# guhPLC_dimmModule_V0_2.net
KiCad netlist of a schematic drawn in EAGLE
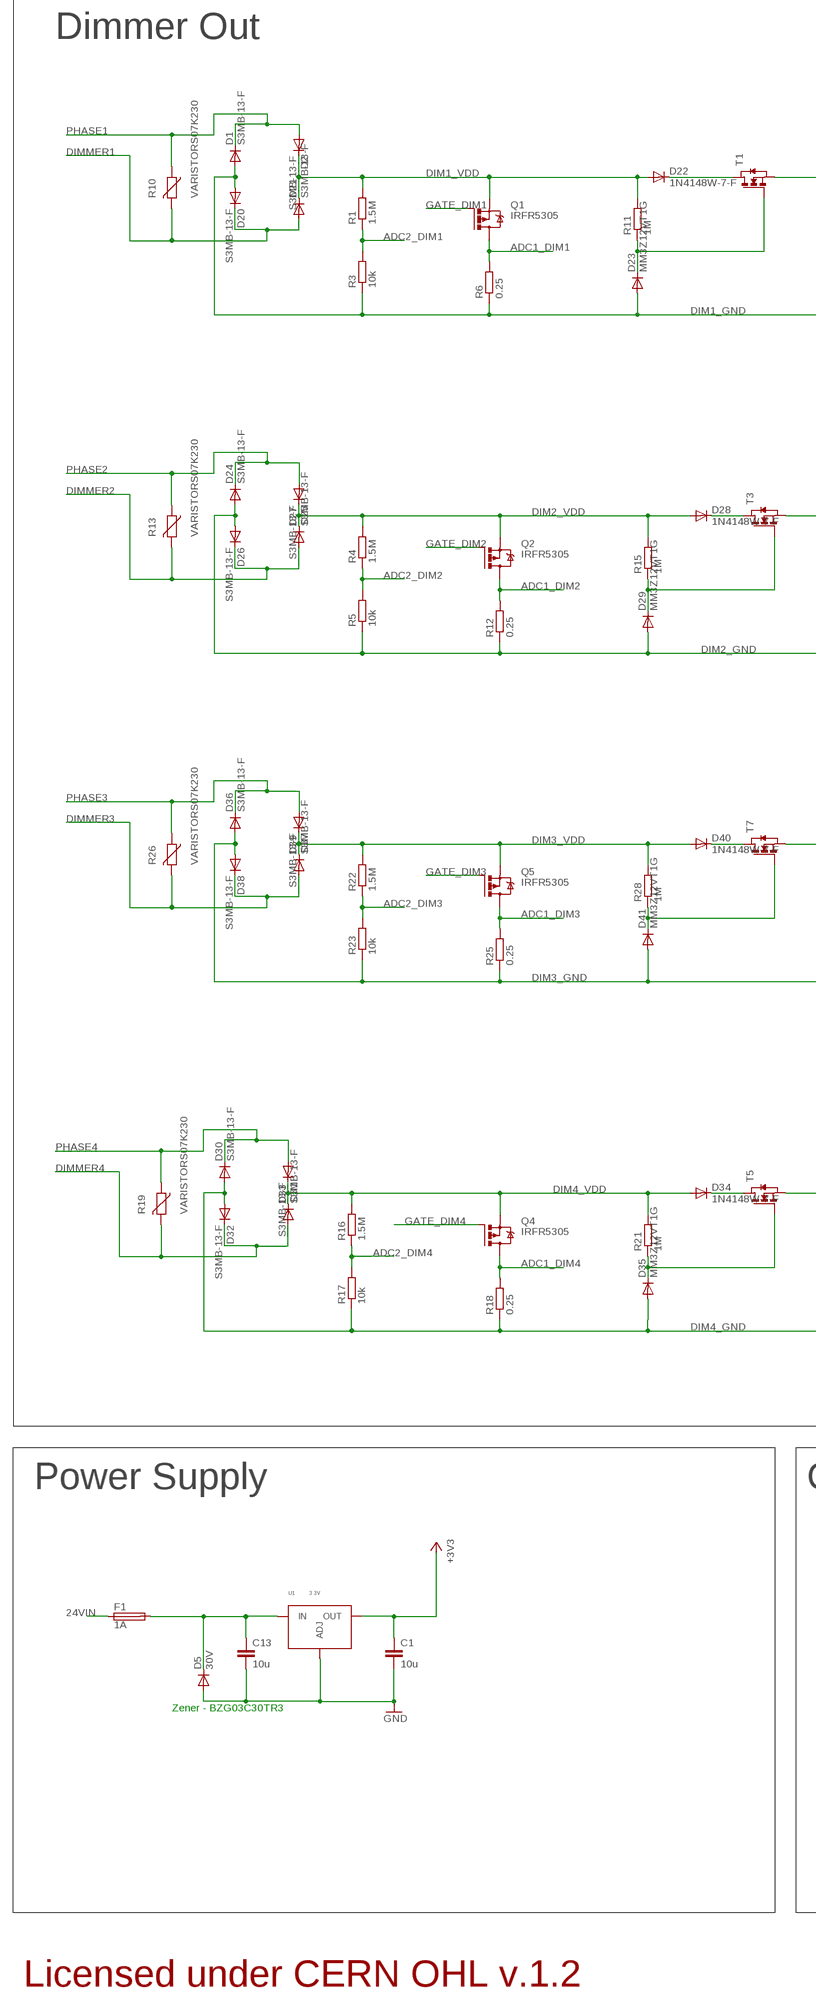
[diagram p0: schematic, sheet 1, part 1 of 2]
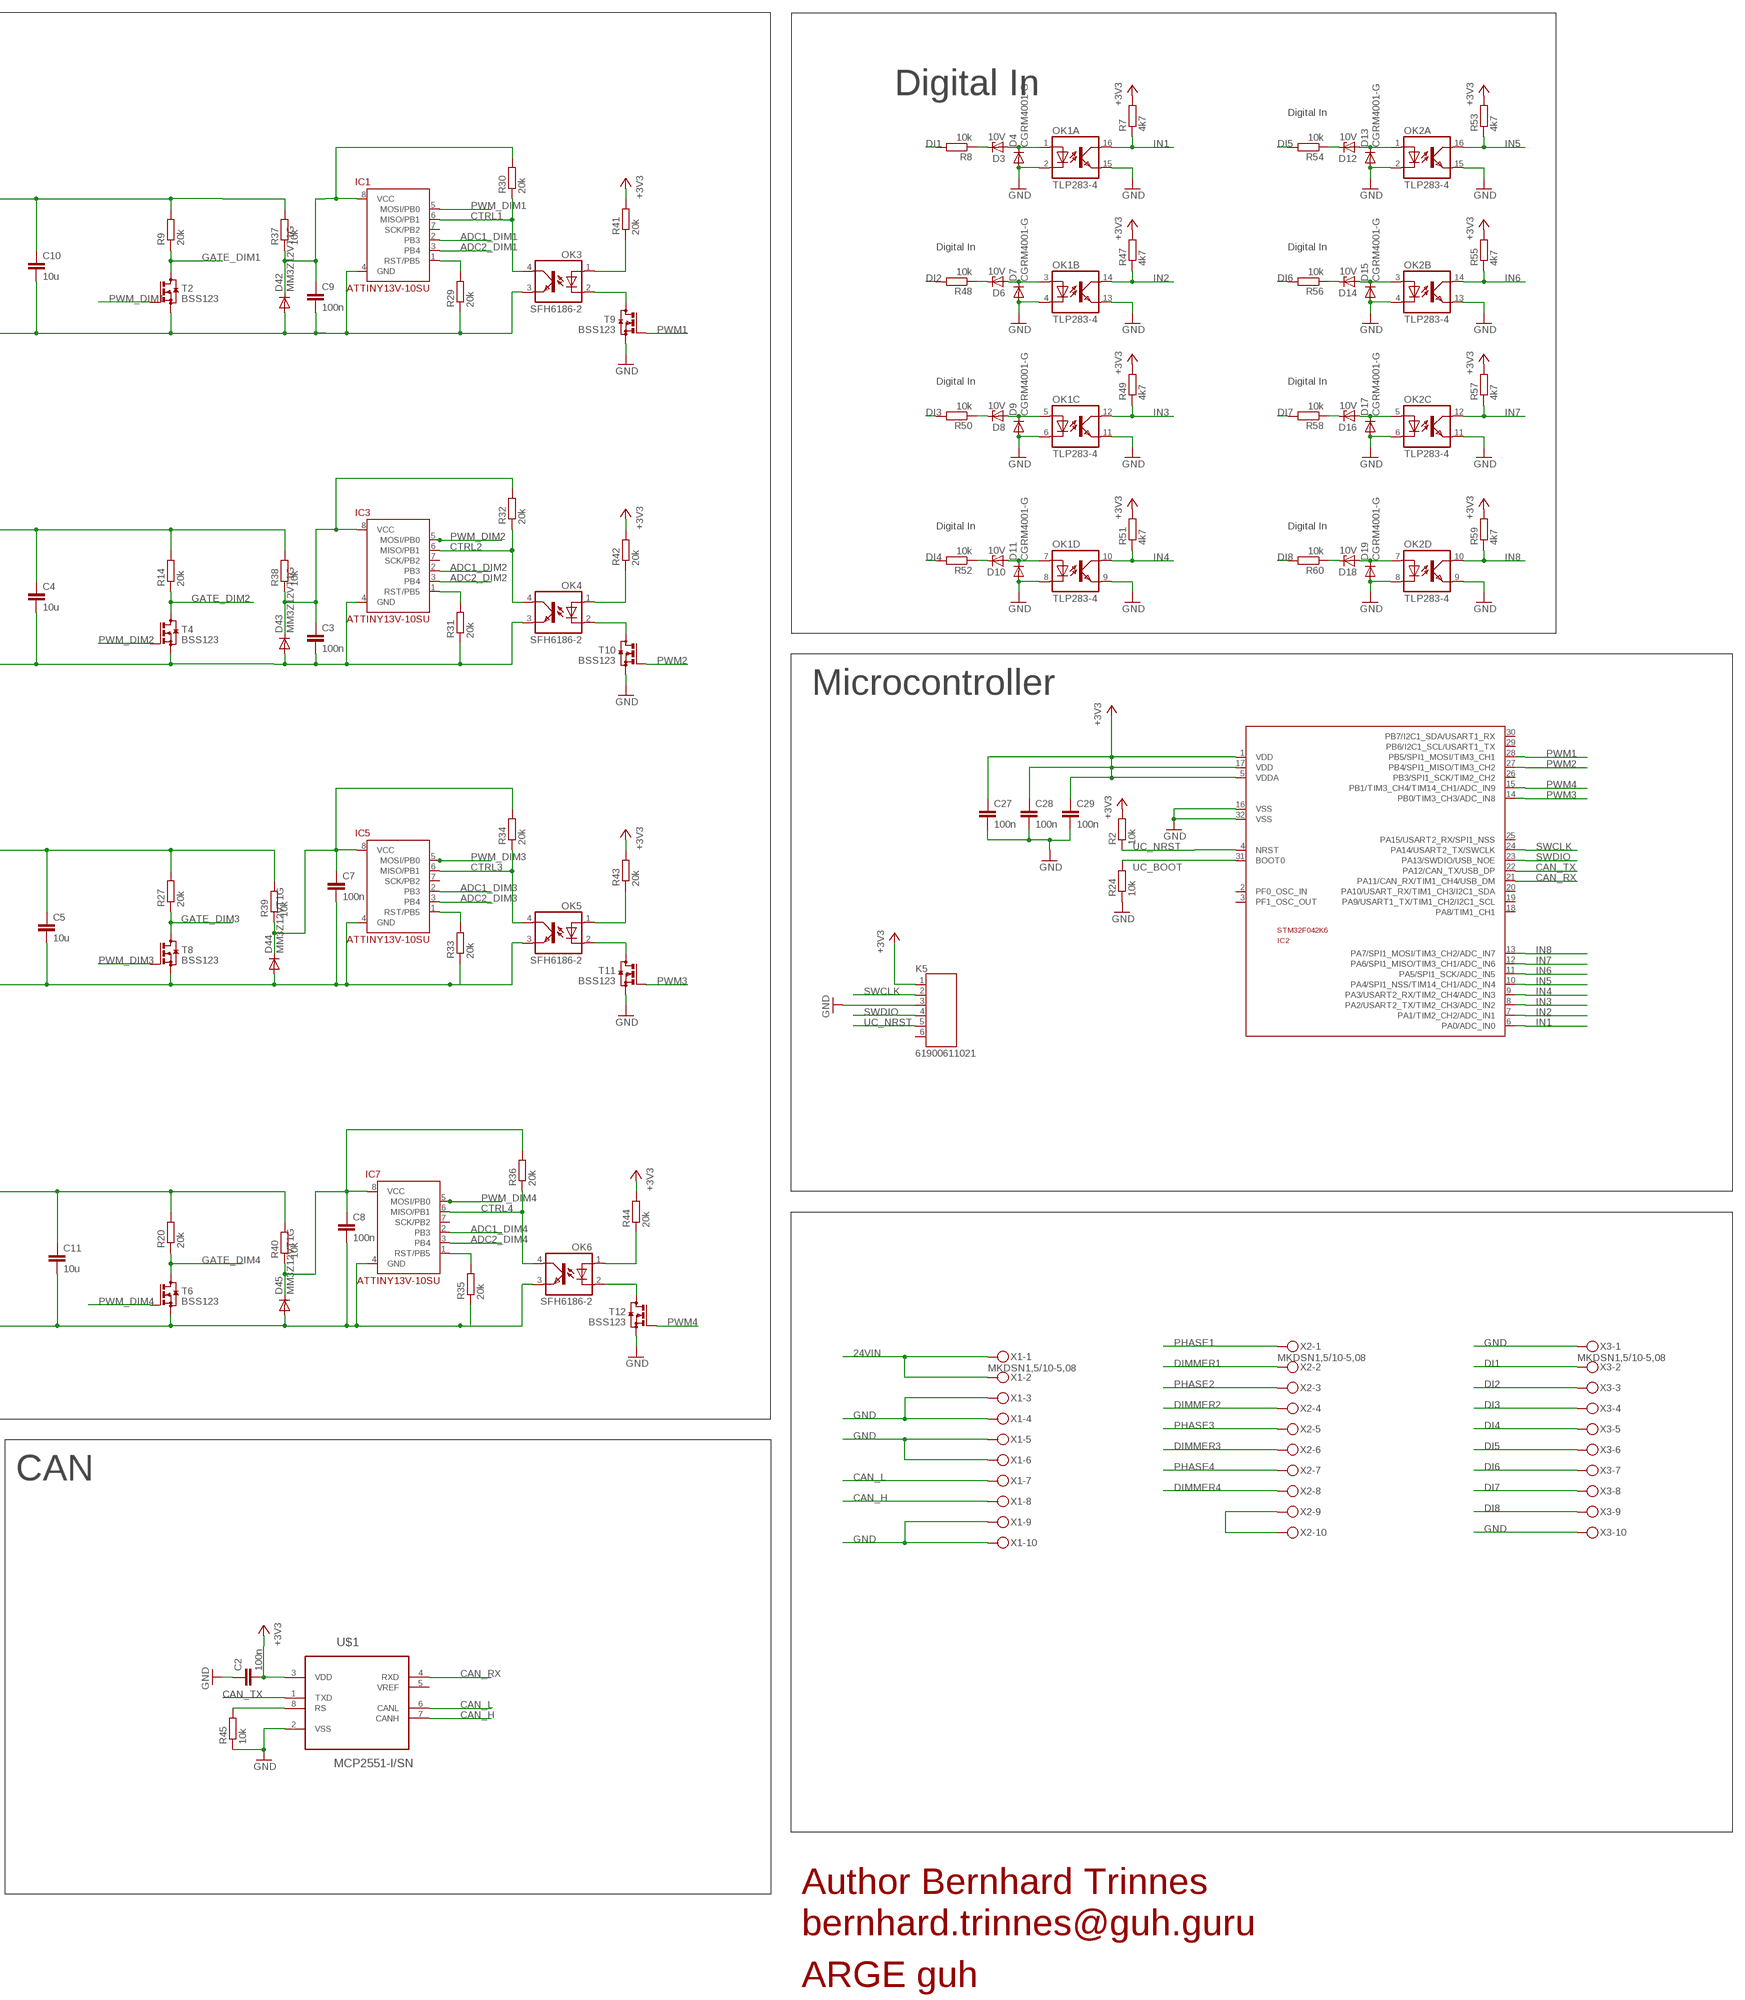
[diagram p1: schematic, sheet 1, part 2 of 2]

(export (version "E")
  (design (tool "Eeschema 10.0.6"))
  (components
    (comp (ref "C1")
      (value "10u")
      (footprint "eagle-import:C1206")
      (libsource (lib "eagle-import") (part "C-EUC1206"))
    )
    (comp (ref "C2")
      (value "100n")
      (footprint "eagle-import:C0603")
      (libsource (lib "eagle-import") (part "C-EUC0603"))
    )
    (comp (ref "C3")
      (value "100n")
      (footprint "eagle-import:C0603")
      (libsource (lib "eagle-import") (part "C-EUC0603"))
    )
    (comp (ref "C4")
      (value "10u")
      (footprint "eagle-import:C1206")
      (libsource (lib "eagle-import") (part "C-EUC1206"))
    )
    (comp (ref "C5")
      (value "10u")
      (footprint "eagle-import:C1206")
      (libsource (lib "eagle-import") (part "C-EUC1206"))
    )
    (comp (ref "C7")
      (value "100n")
      (footprint "eagle-import:C0603")
      (libsource (lib "eagle-import") (part "C-EUC0603"))
    )
    (comp (ref "C8")
      (value "100n")
      (footprint "eagle-import:C0603")
      (libsource (lib "eagle-import") (part "C-EUC0603"))
    )
    (comp (ref "C9")
      (value "100n")
      (footprint "eagle-import:C0603")
      (libsource (lib "eagle-import") (part "C-EUC0603"))
    )
    (comp (ref "C10")
      (value "10u")
      (footprint "eagle-import:C1206")
      (libsource (lib "eagle-import") (part "C-EUC1206"))
    )
    (comp (ref "C11")
      (value "10u")
      (footprint "eagle-import:C1206")
      (libsource (lib "eagle-import") (part "C-EUC1206"))
    )
    (comp (ref "C13")
      (value "10u")
      (footprint "eagle-import:C1206")
      (libsource (lib "eagle-import") (part "C-EUC1206"))
    )
    (comp (ref "C27")
      (value "100n")
      (footprint "eagle-import:C0603")
      (libsource (lib "eagle-import") (part "C-EUC0603"))
    )
    (comp (ref "C28")
      (value "100n")
      (footprint "eagle-import:C0603")
      (libsource (lib "eagle-import") (part "C-EUC0603"))
    )
    (comp (ref "C29")
      (value "100n")
      (footprint "eagle-import:C0603")
      (libsource (lib "eagle-import") (part "C-EUC0603"))
    )
    (comp (ref "D1")
      (value "S3MB-13-F")
      (footprint "eagle-import:DO214AA")
      (libsource (lib "eagle-import") (part "DIODE-DO214AA"))
    )
    (comp (ref "D2")
      (value "S3MB-13-F")
      (footprint "eagle-import:DO214AA")
      (libsource (lib "eagle-import") (part "DIODE-DO214AA"))
    )
    (comp (ref "D3")
      (value "10V")
      (footprint "eagle-import:SOD80C")
      (libsource (lib "eagle-import") (part "ZENER-DIODESOD80C"))
    )
    (comp (ref "D4")
      (value "CGRM4001-G")
      (footprint "eagle-import:SOD-123_MINI-SMA")
      (libsource (lib "eagle-import") (part "CGRM400-G1"))
    )
    (comp (ref "D5")
      (value "30V")
      (footprint "eagle-import:DO214AC")
      (libsource (lib "eagle-import") (part "DIODE-DO214AC"))
    )
    (comp (ref "D6")
      (value "10V")
      (footprint "eagle-import:SOD80C")
      (libsource (lib "eagle-import") (part "ZENER-DIODESOD80C"))
    )
    (comp (ref "D7")
      (value "CGRM4001-G")
      (footprint "eagle-import:SOD-123_MINI-SMA")
      (libsource (lib "eagle-import") (part "CGRM400-G1"))
    )
    (comp (ref "D8")
      (value "10V")
      (footprint "eagle-import:SOD80C")
      (libsource (lib "eagle-import") (part "ZENER-DIODESOD80C"))
    )
    (comp (ref "D9")
      (value "CGRM4001-G")
      (footprint "eagle-import:SOD-123_MINI-SMA")
      (libsource (lib "eagle-import") (part "CGRM400-G1"))
    )
    (comp (ref "D10")
      (value "10V")
      (footprint "eagle-import:SOD80C")
      (libsource (lib "eagle-import") (part "ZENER-DIODESOD80C"))
    )
    (comp (ref "D11")
      (value "CGRM4001-G")
      (footprint "eagle-import:SOD-123_MINI-SMA")
      (libsource (lib "eagle-import") (part "CGRM400-G1"))
    )
    (comp (ref "D12")
      (value "10V")
      (footprint "eagle-import:SOD80C")
      (libsource (lib "eagle-import") (part "ZENER-DIODESOD80C"))
    )
    (comp (ref "D13")
      (value "CGRM4001-G")
      (footprint "eagle-import:SOD-123_MINI-SMA")
      (libsource (lib "eagle-import") (part "CGRM400-G1"))
    )
    (comp (ref "D14")
      (value "10V")
      (footprint "eagle-import:SOD80C")
      (libsource (lib "eagle-import") (part "ZENER-DIODESOD80C"))
    )
    (comp (ref "D15")
      (value "CGRM4001-G")
      (footprint "eagle-import:SOD-123_MINI-SMA")
      (libsource (lib "eagle-import") (part "CGRM400-G1"))
    )
    (comp (ref "D16")
      (value "10V")
      (footprint "eagle-import:SOD80C")
      (libsource (lib "eagle-import") (part "ZENER-DIODESOD80C"))
    )
    (comp (ref "D17")
      (value "CGRM4001-G")
      (footprint "eagle-import:SOD-123_MINI-SMA")
      (libsource (lib "eagle-import") (part "CGRM400-G1"))
    )
    (comp (ref "D18")
      (value "10V")
      (footprint "eagle-import:SOD80C")
      (libsource (lib "eagle-import") (part "ZENER-DIODESOD80C"))
    )
    (comp (ref "D19")
      (value "CGRM4001-G")
      (footprint "eagle-import:SOD-123_MINI-SMA")
      (libsource (lib "eagle-import") (part "CGRM400-G1"))
    )
    (comp (ref "D20")
      (value "S3MB-13-F")
      (footprint "eagle-import:DO214AA")
      (libsource (lib "eagle-import") (part "DIODE-DO214AA"))
    )
    (comp (ref "D21")
      (value "S3MB-13-F")
      (footprint "eagle-import:DO214AA")
      (libsource (lib "eagle-import") (part "DIODE-DO214AA"))
    )
    (comp (ref "D22")
      (value "1N4148W-7-F")
      (footprint "eagle-import:SOD123")
      (libsource (lib "eagle-import") (part "DIODE-SOD123"))
    )
    (comp (ref "D23")
      (value "MM3Z12VT1G")
      (footprint "eagle-import:SOD323-W")
      (libsource (lib "eagle-import") (part "DIODE-SOD323-W"))
    )
    (comp (ref "D24")
      (value "S3MB-13-F")
      (footprint "eagle-import:DO214AA")
      (libsource (lib "eagle-import") (part "DIODE-DO214AA"))
    )
    (comp (ref "D25")
      (value "S3MB-13-F")
      (footprint "eagle-import:DO214AA")
      (libsource (lib "eagle-import") (part "DIODE-DO214AA"))
    )
    (comp (ref "D26")
      (value "S3MB-13-F")
      (footprint "eagle-import:DO214AA")
      (libsource (lib "eagle-import") (part "DIODE-DO214AA"))
    )
    (comp (ref "D27")
      (value "S3MB-13-F")
      (footprint "eagle-import:DO214AA")
      (libsource (lib "eagle-import") (part "DIODE-DO214AA"))
    )
    (comp (ref "D28")
      (value "1N4148W-7-F")
      (footprint "eagle-import:SOD123")
      (libsource (lib "eagle-import") (part "DIODE-SOD123"))
    )
    (comp (ref "D29")
      (value "MM3Z12VT1G")
      (footprint "eagle-import:SOD323-W")
      (libsource (lib "eagle-import") (part "guh_DIODE-SOD323-W"))
    )
    (comp (ref "D30")
      (value "S3MB-13-F")
      (footprint "eagle-import:DO214AA")
      (libsource (lib "eagle-import") (part "DIODE-DO214AA"))
    )
    (comp (ref "D31")
      (value "S3MB-13-F")
      (footprint "eagle-import:DO214AA")
      (libsource (lib "eagle-import") (part "DIODE-DO214AA"))
    )
    (comp (ref "D32")
      (value "S3MB-13-F")
      (footprint "eagle-import:DO214AA")
      (libsource (lib "eagle-import") (part "DIODE-DO214AA"))
    )
    (comp (ref "D33")
      (value "S3MB-13-F")
      (footprint "eagle-import:DO214AA")
      (libsource (lib "eagle-import") (part "DIODE-DO214AA"))
    )
    (comp (ref "D34")
      (value "1N4148W-7-F")
      (footprint "eagle-import:SOD123")
      (libsource (lib "eagle-import") (part "DIODE-SOD123"))
    )
    (comp (ref "D35")
      (value "MM3Z12VT1G")
      (footprint "eagle-import:SOD323-W")
      (libsource (lib "eagle-import") (part "guh_DIODE-SOD323-W"))
    )
    (comp (ref "D36")
      (value "S3MB-13-F")
      (footprint "eagle-import:DO214AA")
      (libsource (lib "eagle-import") (part "DIODE-DO214AA"))
    )
    (comp (ref "D37")
      (value "S3MB-13-F")
      (footprint "eagle-import:DO214AA")
      (libsource (lib "eagle-import") (part "DIODE-DO214AA"))
    )
    (comp (ref "D38")
      (value "S3MB-13-F")
      (footprint "eagle-import:DO214AA")
      (libsource (lib "eagle-import") (part "DIODE-DO214AA"))
    )
    (comp (ref "D39")
      (value "S3MB-13-F")
      (footprint "eagle-import:DO214AA")
      (libsource (lib "eagle-import") (part "DIODE-DO214AA"))
    )
    (comp (ref "D40")
      (value "1N4148W-7-F")
      (footprint "eagle-import:SOD123")
      (libsource (lib "eagle-import") (part "DIODE-SOD123"))
    )
    (comp (ref "D41")
      (value "MM3Z12VT1G")
      (footprint "eagle-import:SOD323-W")
      (libsource (lib "eagle-import") (part "guh_DIODE-SOD323-W"))
    )
    (comp (ref "D42")
      (value "MM3Z12VT1G")
      (footprint "eagle-import:SOD323-W")
      (libsource (lib "eagle-import") (part "DIODE-SOD323-W"))
    )
    (comp (ref "D43")
      (value "MM3Z12VT1G")
      (footprint "eagle-import:SOD323-W")
      (libsource (lib "eagle-import") (part "DIODE-SOD323-W"))
    )
    (comp (ref "D44")
      (value "MM3Z12VT1G")
      (footprint "eagle-import:SOD323-W")
      (libsource (lib "eagle-import") (part "DIODE-SOD323-W"))
    )
    (comp (ref "D45")
      (value "MM3Z12VT1G")
      (footprint "eagle-import:SOD323-W")
      (libsource (lib "eagle-import") (part "DIODE-SOD323-W"))
    )
    (comp (ref "F1")
      (value "1A")
      (footprint "eagle-import:LITTLEFUSE")
      (libsource (lib "eagle-import") (part "LITTLEFUSE"))
    )
    (comp (ref "IC1")
      (value "ATTINY13V-10SU")
      (footprint "eagle-import:SOIC8")
      (libsource (lib "eagle-import") (part "ATTINY13V-10SU"))
    )
    (comp (ref "IC2")
      (value "STM32F042K6")
      (footprint "eagle-import:LQFP32-7X7")
      (libsource (lib "eagle-import") (part "STM32F042K6"))
    )
    (comp (ref "IC3")
      (value "ATTINY13V-10SU")
      (footprint "eagle-import:SOIC8")
      (libsource (lib "eagle-import") (part "ATTINY13V-10SU"))
    )
    (comp (ref "IC5")
      (value "ATTINY13V-10SU")
      (footprint "eagle-import:SOIC8")
      (libsource (lib "eagle-import") (part "ATTINY13V-10SU"))
    )
    (comp (ref "IC7")
      (value "ATTINY13V-10SU")
      (footprint "eagle-import:SOIC8")
      (libsource (lib "eagle-import") (part "ATTINY13V-10SU"))
    )
    (comp (ref "K5")
      (value "61900611021")
      (footprint "eagle-import:61900611021")
      (libsource (lib "eagle-import") (part "61900611021"))
    )
    (comp (ref "OK1")
      (value "TLP283-4")
      (footprint "eagle-import:MINI-FLAT-16")
      (libsource (lib "eagle-import") (part "TLP283-4"))
    )
    (comp (ref "OK2")
      (value "TLP283-4")
      (footprint "eagle-import:MINI-FLAT-16")
      (libsource (lib "eagle-import") (part "TLP283-4"))
    )
    (comp (ref "OK3")
      (value "SFH6186-2")
      (footprint "eagle-import:SMD4")
      (fields (field (name "MF") "VISHAY/TELEFUNKEN"))
      (libsource (lib "eagle-import") (part "SFH618?6-2"))
    )
    (comp (ref "OK4")
      (value "SFH6186-2")
      (footprint "eagle-import:SMD4")
      (fields (field (name "MF") "VISHAY/TELEFUNKEN"))
      (libsource (lib "eagle-import") (part "SFH618?6-2"))
    )
    (comp (ref "OK5")
      (value "SFH6186-2")
      (footprint "eagle-import:SMD4")
      (fields (field (name "MF") "VISHAY/TELEFUNKEN"))
      (libsource (lib "eagle-import") (part "SFH618?6-2"))
    )
    (comp (ref "OK6")
      (value "SFH6186-2")
      (footprint "eagle-import:SMD4")
      (fields (field (name "MF") "VISHAY/TELEFUNKEN"))
      (libsource (lib "eagle-import") (part "SFH618?6-2"))
    )
    (comp (ref "Q1")
      (value "IRFR5305")
      (footprint "eagle-import:D-PAK_TO252AA")
      (libsource (lib "eagle-import") (part "IRF?5305R"))
    )
    (comp (ref "Q2")
      (value "IRFR5305")
      (footprint "eagle-import:D-PAK_TO252AA")
      (libsource (lib "eagle-import") (part "IRF?5305R"))
    )
    (comp (ref "Q4")
      (value "IRFR5305")
      (footprint "eagle-import:D-PAK_TO252AA")
      (libsource (lib "eagle-import") (part "IRF?5305R"))
    )
    (comp (ref "Q5")
      (value "IRFR5305")
      (footprint "eagle-import:D-PAK_TO252AA")
      (libsource (lib "eagle-import") (part "IRF?5305R"))
    )
    (comp (ref "R1")
      (value "1.5M")
      (footprint "eagle-import:R1206")
      (libsource (lib "eagle-import") (part "R-EU_R1206"))
    )
    (comp (ref "R2")
      (value "10k")
      (footprint "eagle-import:R0603")
      (libsource (lib "eagle-import") (part "R-EU_R0603"))
    )
    (comp (ref "R3")
      (value "10k")
      (footprint "eagle-import:R1206")
      (libsource (lib "eagle-import") (part "R-EU_R1206"))
    )
    (comp (ref "R4")
      (value "1.5M")
      (footprint "eagle-import:M1206")
      (libsource (lib "eagle-import") (part "R-EU_M1206"))
    )
    (comp (ref "R5")
      (value "10k")
      (footprint "eagle-import:M1206")
      (libsource (lib "eagle-import") (part "R-EU_M1206"))
    )
    (comp (ref "R6")
      (value "0.25")
      (footprint "eagle-import:R1206")
      (libsource (lib "eagle-import") (part "R-EU_R1206"))
    )
    (comp (ref "R7")
      (value "4k7")
      (footprint "eagle-import:R0603")
      (libsource (lib "eagle-import") (part "R-EU_R0603"))
    )
    (comp (ref "R8")
      (value "10k")
      (footprint "eagle-import:R0805")
      (libsource (lib "eagle-import") (part "R-EU_R0805"))
    )
    (comp (ref "R9")
      (value "20k")
      (footprint "eagle-import:M1206")
      (libsource (lib "eagle-import") (part "R-EU_M1206"))
    )
    (comp (ref "R10")
      (value "VARISTORS07K230")
      (footprint "eagle-import:S07K230")
      (libsource (lib "eagle-import") (part "VARISTORS07K230"))
    )
    (comp (ref "R11")
      (value "1M")
      (footprint "eagle-import:R1206")
      (libsource (lib "eagle-import") (part "R-EU_R1206"))
    )
    (comp (ref "R12")
      (value "0.25")
      (footprint "eagle-import:M1206")
      (libsource (lib "eagle-import") (part "R-EU_M1206"))
    )
    (comp (ref "R13")
      (value "VARISTORS07K230")
      (footprint "eagle-import:S07K230")
      (libsource (lib "eagle-import") (part "VARISTORS07K230"))
    )
    (comp (ref "R14")
      (value "20k")
      (footprint "eagle-import:M1206")
      (libsource (lib "eagle-import") (part "R-EU_M1206"))
    )
    (comp (ref "R15")
      (value "1M")
      (footprint "eagle-import:M1206")
      (libsource (lib "eagle-import") (part "R-EU_M1206"))
    )
    (comp (ref "R16")
      (value "1.5M")
      (footprint "eagle-import:M1206")
      (libsource (lib "eagle-import") (part "R-EU_M1206"))
    )
    (comp (ref "R17")
      (value "10k")
      (footprint "eagle-import:M1206")
      (libsource (lib "eagle-import") (part "R-EU_M1206"))
    )
    (comp (ref "R18")
      (value "0.25")
      (footprint "eagle-import:M1206")
      (libsource (lib "eagle-import") (part "R-EU_M1206"))
    )
    (comp (ref "R19")
      (value "VARISTORS07K230")
      (footprint "eagle-import:S07K230")
      (libsource (lib "eagle-import") (part "VARISTORS07K230"))
    )
    (comp (ref "R20")
      (value "20k")
      (footprint "eagle-import:M1206")
      (libsource (lib "eagle-import") (part "R-EU_M1206"))
    )
    (comp (ref "R21")
      (value "1M")
      (footprint "eagle-import:M1206")
      (libsource (lib "eagle-import") (part "R-EU_M1206"))
    )
    (comp (ref "R22")
      (value "1.5M")
      (footprint "eagle-import:M1206")
      (libsource (lib "eagle-import") (part "R-EU_M1206"))
    )
    (comp (ref "R23")
      (value "10k")
      (footprint "eagle-import:M1206")
      (libsource (lib "eagle-import") (part "R-EU_M1206"))
    )
    (comp (ref "R24")
      (value "10k")
      (footprint "eagle-import:R0603")
      (libsource (lib "eagle-import") (part "R-EU_R0603"))
    )
    (comp (ref "R25")
      (value "0.25")
      (footprint "eagle-import:M1206")
      (libsource (lib "eagle-import") (part "R-EU_M1206"))
    )
    (comp (ref "R26")
      (value "VARISTORS07K230")
      (footprint "eagle-import:S07K230")
      (libsource (lib "eagle-import") (part "VARISTORS07K230"))
    )
    (comp (ref "R27")
      (value "20k")
      (footprint "eagle-import:M1206")
      (libsource (lib "eagle-import") (part "R-EU_M1206"))
    )
    (comp (ref "R28")
      (value "1M")
      (footprint "eagle-import:M1206")
      (libsource (lib "eagle-import") (part "R-EU_M1206"))
    )
    (comp (ref "R29")
      (value "20k")
      (footprint "eagle-import:R0603")
      (libsource (lib "eagle-import") (part "R-EU_R0603"))
    )
    (comp (ref "R30")
      (value "20k")
      (footprint "eagle-import:R0603")
      (libsource (lib "eagle-import") (part "R-EU_R0603"))
    )
    (comp (ref "R31")
      (value "20k")
      (footprint "eagle-import:R0603")
      (libsource (lib "eagle-import") (part "R-EU_R0603"))
    )
    (comp (ref "R32")
      (value "20k")
      (footprint "eagle-import:R0603")
      (libsource (lib "eagle-import") (part "R-EU_R0603"))
    )
    (comp (ref "R33")
      (value "20k")
      (footprint "eagle-import:R0603")
      (libsource (lib "eagle-import") (part "R-EU_R0603"))
    )
    (comp (ref "R34")
      (value "20k")
      (footprint "eagle-import:R0603")
      (libsource (lib "eagle-import") (part "R-EU_R0603"))
    )
    (comp (ref "R35")
      (value "20k")
      (footprint "eagle-import:R0603")
      (libsource (lib "eagle-import") (part "R-EU_R0603"))
    )
    (comp (ref "R36")
      (value "20k")
      (footprint "eagle-import:R0603")
      (libsource (lib "eagle-import") (part "R-EU_R0603"))
    )
    (comp (ref "R37")
      (value "10k")
      (footprint "eagle-import:M1206")
      (libsource (lib "eagle-import") (part "R-EU_M1206"))
    )
    (comp (ref "R38")
      (value "10k")
      (footprint "eagle-import:M1206")
      (libsource (lib "eagle-import") (part "R-EU_M1206"))
    )
    (comp (ref "R39")
      (value "10k")
      (footprint "eagle-import:M1206")
      (libsource (lib "eagle-import") (part "R-EU_M1206"))
    )
    (comp (ref "R40")
      (value "10k")
      (footprint "eagle-import:M1206")
      (libsource (lib "eagle-import") (part "R-EU_M1206"))
    )
    (comp (ref "R41")
      (value "20k")
      (footprint "eagle-import:R0603")
      (libsource (lib "eagle-import") (part "R-EU_R0603"))
    )
    (comp (ref "R42")
      (value "20k")
      (footprint "eagle-import:R0603")
      (libsource (lib "eagle-import") (part "R-EU_R0603"))
    )
    (comp (ref "R43")
      (value "20k")
      (footprint "eagle-import:R0603")
      (libsource (lib "eagle-import") (part "R-EU_R0603"))
    )
    (comp (ref "R44")
      (value "20k")
      (footprint "eagle-import:R0603")
      (libsource (lib "eagle-import") (part "R-EU_R0603"))
    )
    (comp (ref "R45")
      (value "10k")
      (footprint "eagle-import:R0603")
      (libsource (lib "eagle-import") (part "R-EU_R0603"))
    )
    (comp (ref "R47")
      (value "4k7")
      (footprint "eagle-import:R0603")
      (libsource (lib "eagle-import") (part "R-EU_R0603"))
    )
    (comp (ref "R48")
      (value "10k")
      (footprint "eagle-import:R0805")
      (libsource (lib "eagle-import") (part "R-EU_R0805"))
    )
    (comp (ref "R49")
      (value "4k7")
      (footprint "eagle-import:R0603")
      (libsource (lib "eagle-import") (part "R-EU_R0603"))
    )
    (comp (ref "R50")
      (value "10k")
      (footprint "eagle-import:R0805")
      (libsource (lib "eagle-import") (part "R-EU_R0805"))
    )
    (comp (ref "R51")
      (value "4k7")
      (footprint "eagle-import:R0603")
      (libsource (lib "eagle-import") (part "R-EU_R0603"))
    )
    (comp (ref "R52")
      (value "10k")
      (footprint "eagle-import:R0805")
      (libsource (lib "eagle-import") (part "R-EU_R0805"))
    )
    (comp (ref "R53")
      (value "4k7")
      (footprint "eagle-import:R0603")
      (libsource (lib "eagle-import") (part "R-EU_R0603"))
    )
    (comp (ref "R54")
      (value "10k")
      (footprint "eagle-import:R0805")
      (libsource (lib "eagle-import") (part "R-EU_R0805"))
    )
    (comp (ref "R55")
      (value "4k7")
      (footprint "eagle-import:R0603")
      (libsource (lib "eagle-import") (part "R-EU_R0603"))
    )
    (comp (ref "R56")
      (value "10k")
      (footprint "eagle-import:R0805")
      (libsource (lib "eagle-import") (part "R-EU_R0805"))
    )
    (comp (ref "R57")
      (value "4k7")
      (footprint "eagle-import:R0603")
      (libsource (lib "eagle-import") (part "R-EU_R0603"))
    )
    (comp (ref "R58")
      (value "10k")
      (footprint "eagle-import:R0805")
      (libsource (lib "eagle-import") (part "R-EU_R0805"))
    )
    (comp (ref "R59")
      (value "4k7")
      (footprint "eagle-import:R0603")
      (libsource (lib "eagle-import") (part "R-EU_R0603"))
    )
    (comp (ref "R60")
      (value "10k")
      (footprint "eagle-import:R0805")
      (libsource (lib "eagle-import") (part "R-EU_R0805"))
    )
    (comp (ref "T1")
      (value "NMOSSOT23")
      (footprint "eagle-import:SOT-23")
      (libsource (lib "eagle-import") (part "NMOSSOT23"))
    )
    (comp (ref "T2")
      (value "BSS123")
      (footprint "eagle-import:SOT23")
      (libsource (lib "eagle-import") (part "BSS123"))
    )
    (comp (ref "T3")
      (value "NMOSSOT23")
      (footprint "eagle-import:SOT-23")
      (libsource (lib "eagle-import") (part "NMOSSOT23"))
    )
    (comp (ref "T4")
      (value "BSS123")
      (footprint "eagle-import:SOT23")
      (libsource (lib "eagle-import") (part "BSS123"))
    )
    (comp (ref "T5")
      (value "NMOSSOT23")
      (footprint "eagle-import:SOT-23")
      (libsource (lib "eagle-import") (part "NMOSSOT23"))
    )
    (comp (ref "T6")
      (value "BSS123")
      (footprint "eagle-import:SOT23")
      (libsource (lib "eagle-import") (part "BSS123"))
    )
    (comp (ref "T7")
      (value "NMOSSOT23")
      (footprint "eagle-import:SOT-23")
      (libsource (lib "eagle-import") (part "NMOSSOT23"))
    )
    (comp (ref "T8")
      (value "BSS123")
      (footprint "eagle-import:SOT23")
      (libsource (lib "eagle-import") (part "BSS123"))
    )
    (comp (ref "T9")
      (value "BSS123")
      (footprint "eagle-import:SOT23")
      (libsource (lib "eagle-import") (part "BSS123"))
    )
    (comp (ref "T10")
      (value "BSS123")
      (footprint "eagle-import:SOT23")
      (libsource (lib "eagle-import") (part "BSS123"))
    )
    (comp (ref "T11")
      (value "BSS123")
      (footprint "eagle-import:SOT23")
      (libsource (lib "eagle-import") (part "BSS123"))
    )
    (comp (ref "T12")
      (value "BSS123")
      (footprint "eagle-import:SOT23")
      (libsource (lib "eagle-import") (part "BSS123"))
    )
    (comp (ref "U$1")
      (value "MCP2551-I/SN")
      (footprint "eagle-import:SOIC127P600X175-8N")
      (libsource (lib "eagle-import") (part "MCP2551-I/SN"))
    )
    (comp (ref "U1")
      (value "3.3V")
      (footprint "eagle-import:TO-252-3L")
      (libsource (lib "eagle-import") (part "ADJ_VOLTAGE_REGTO-252-3L"))
    )
    (comp (ref "X1")
      (value "MKDSN1,5/10-5,08")
      (footprint "eagle-import:MKDSN1,5_10-5,08")
      (fields (field (name "MPN") "SMKDSN1,5/10-5,08"))
      (libsource (lib "eagle-import") (part "MKDSN1,5/10-5,08"))
    )
    (comp (ref "X2")
      (value "MKDSN1,5/10-5,08")
      (footprint "eagle-import:MKDSN1,5_10-5,08")
      (fields (field (name "MPN") "SMKDSN1,5/10-5,08"))
      (libsource (lib "eagle-import") (part "MKDSN1,5/10-5,08"))
    )
    (comp (ref "X3")
      (value "MKDSN1,5/10-5,08")
      (footprint "eagle-import:MKDSN1,5_10-5,08")
      (fields (field (name "MPN") "SMKDSN1,5/10-5,08"))
      (libsource (lib "eagle-import") (part "MKDSN1,5/10-5,08"))
    )
  )
  (nets
    (net (code "1") (name "+3V3") (class "Default")
      (node (ref "C1") (pin "1") (pinfunction "1_1") (pintype "passive"))
      (node (ref "C2") (pin "2") (pinfunction "2_2") (pintype "passive"))
      (node (ref "C27") (pin "1") (pinfunction "1_1") (pintype "passive"))
      (node (ref "C28") (pin "1") (pinfunction "1_1") (pintype "passive"))
      (node (ref "C29") (pin "1") (pinfunction "1_1") (pintype "passive"))
      (node (ref "IC2") (pin "1") (pinfunction "VDD_1") (pintype "power_in"))
      (node (ref "IC2") (pin "17") (pinfunction "VDD_17") (pintype "power_in"))
      (node (ref "IC2") (pin "5") (pinfunction "VDDA_5") (pintype "power_in"))
      (node (ref "K5") (pin "1") (pinfunction "1_1") (pintype "passive"))
      (node (ref "R2") (pin "2") (pinfunction "2_2") (pintype "passive"))
      (node (ref "R41") (pin "2") (pinfunction "2_2") (pintype "passive"))
      (node (ref "R42") (pin "2") (pinfunction "2_2") (pintype "passive"))
      (node (ref "R43") (pin "2") (pinfunction "2_2") (pintype "passive"))
      (node (ref "R44") (pin "2") (pinfunction "2_2") (pintype "passive"))
      (node (ref "R47") (pin "2") (pinfunction "2_2") (pintype "passive"))
      (node (ref "R49") (pin "2") (pinfunction "2_2") (pintype "passive"))
      (node (ref "R51") (pin "2") (pinfunction "2_2") (pintype "passive"))
      (node (ref "R53") (pin "2") (pinfunction "2_2") (pintype "passive"))
      (node (ref "R55") (pin "2") (pinfunction "2_2") (pintype "passive"))
      (node (ref "R57") (pin "2") (pinfunction "2_2") (pintype "passive"))
      (node (ref "R59") (pin "2") (pinfunction "2_2") (pintype "passive"))
      (node (ref "R7") (pin "2") (pinfunction "2_2") (pintype "passive"))
      (node (ref "U$1") (pin "3") (pinfunction "VDD_3") (pintype "power_in"))
      (node (ref "U1") (pin "PAD") (pinfunction "OUT_PAD") (pintype "bidirectional"))
    )
    (net (code "2") (name "/24VIN") (class "Default")
      (node (ref "F1") (pin "1") (pinfunction "1_1") (pintype "passive"))
      (node (ref "X1") (pin "1") (pinfunction "KL_1") (pintype "passive"))
      (node (ref "X1") (pin "2") (pinfunction "KL_2") (pintype "passive"))
    )
    (net (code "3") (name "/ADC1_DIM1") (class "Default")
      (node (ref "IC1") (pin "2") (pinfunction "PB3_2") (pintype "bidirectional"))
      (node (ref "Q1") (pin "4") (pinfunction "D_4") (pintype "passive"))
      (node (ref "R6") (pin "2") (pinfunction "2_2") (pintype "passive"))
    )
    (net (code "4") (name "/ADC1_DIM2") (class "Default")
      (node (ref "IC3") (pin "2") (pinfunction "PB3_2") (pintype "bidirectional"))
      (node (ref "Q2") (pin "4") (pinfunction "D_4") (pintype "passive"))
      (node (ref "R12") (pin "2") (pinfunction "2_2") (pintype "passive"))
    )
    (net (code "5") (name "/ADC1_DIM3") (class "Default")
      (node (ref "IC5") (pin "2") (pinfunction "PB3_2") (pintype "bidirectional"))
      (node (ref "Q5") (pin "4") (pinfunction "D_4") (pintype "passive"))
      (node (ref "R25") (pin "2") (pinfunction "2_2") (pintype "passive"))
    )
    (net (code "6") (name "/ADC1_DIM4") (class "Default")
      (node (ref "IC7") (pin "2") (pinfunction "PB3_2") (pintype "bidirectional"))
      (node (ref "Q4") (pin "4") (pinfunction "D_4") (pintype "passive"))
      (node (ref "R18") (pin "2") (pinfunction "2_2") (pintype "passive"))
    )
    (net (code "7") (name "/ADC2_DIM1") (class "Default")
      (node (ref "IC1") (pin "3") (pinfunction "PB4_3") (pintype "bidirectional"))
      (node (ref "R1") (pin "1") (pinfunction "1_1") (pintype "passive"))
      (node (ref "R3") (pin "2") (pinfunction "2_2") (pintype "passive"))
    )
    (net (code "8") (name "/ADC2_DIM2") (class "Default")
      (node (ref "IC3") (pin "3") (pinfunction "PB4_3") (pintype "bidirectional"))
      (node (ref "R4") (pin "1") (pinfunction "1_1") (pintype "passive"))
      (node (ref "R5") (pin "2") (pinfunction "2_2") (pintype "passive"))
    )
    (net (code "9") (name "/ADC2_DIM3") (class "Default")
      (node (ref "IC5") (pin "3") (pinfunction "PB4_3") (pintype "bidirectional"))
      (node (ref "R22") (pin "1") (pinfunction "1_1") (pintype "passive"))
      (node (ref "R23") (pin "2") (pinfunction "2_2") (pintype "passive"))
    )
    (net (code "10") (name "/ADC2_DIM4") (class "Default")
      (node (ref "IC7") (pin "3") (pinfunction "PB4_3") (pintype "bidirectional"))
      (node (ref "R16") (pin "1") (pinfunction "1_1") (pintype "passive"))
      (node (ref "R17") (pin "2") (pinfunction "2_2") (pintype "passive"))
    )
    (net (code "11") (name "/CAN_H") (class "Default")
      (node (ref "U$1") (pin "7") (pinfunction "CANH_7") (pintype "bidirectional"))
      (node (ref "X1") (pin "8") (pinfunction "KL_8") (pintype "passive"))
    )
    (net (code "12") (name "/CAN_L") (class "Default")
      (node (ref "U$1") (pin "6") (pinfunction "CANL_6") (pintype "bidirectional"))
      (node (ref "X1") (pin "7") (pinfunction "KL_7") (pintype "passive"))
    )
    (net (code "13") (name "/CAN_RX") (class "Default")
      (node (ref "IC2") (pin "21") (pinfunction "PA11/CAN_RX/TIM1_CH4/USB_DM_21") (pintype "bidirectional"))
      (node (ref "U$1") (pin "4") (pinfunction "RXD_4") (pintype "output"))
    )
    (net (code "14") (name "/CAN_TX") (class "Default")
      (node (ref "IC2") (pin "22") (pinfunction "PA12/CAN_TX/USB_DP_22") (pintype "bidirectional"))
      (node (ref "U$1") (pin "1") (pinfunction "TXD_1") (pintype "input"))
    )
    (net (code "15") (name "/CTRL1") (class "Default")
      (node (ref "IC1") (pin "6") (pinfunction "MISO/PB1_6") (pintype "bidirectional"))
      (node (ref "OK3") (pin "4") (pinfunction "COL_4") (pintype "passive"))
      (node (ref "R30") (pin "1") (pinfunction "1_1") (pintype "passive"))
    )
    (net (code "16") (name "/CTRL2") (class "Default")
      (node (ref "IC3") (pin "6") (pinfunction "MISO/PB1_6") (pintype "bidirectional"))
      (node (ref "OK4") (pin "4") (pinfunction "COL_4") (pintype "passive"))
      (node (ref "R32") (pin "1") (pinfunction "1_1") (pintype "passive"))
    )
    (net (code "17") (name "/CTRL3") (class "Default")
      (node (ref "IC5") (pin "6") (pinfunction "MISO/PB1_6") (pintype "bidirectional"))
      (node (ref "OK5") (pin "4") (pinfunction "COL_4") (pintype "passive"))
      (node (ref "R34") (pin "1") (pinfunction "1_1") (pintype "passive"))
    )
    (net (code "18") (name "/CTRL4") (class "Default")
      (node (ref "IC7") (pin "6") (pinfunction "MISO/PB1_6") (pintype "bidirectional"))
      (node (ref "OK6") (pin "4") (pinfunction "COL_4") (pintype "passive"))
      (node (ref "R36") (pin "1") (pinfunction "1_1") (pintype "passive"))
    )
    (net (code "19") (name "/DI1") (class "Default")
      (node (ref "R8") (pin "2") (pinfunction "2_2") (pintype "passive"))
      (node (ref "X3") (pin "2") (pinfunction "KL_2") (pintype "passive"))
    )
    (net (code "20") (name "/DI2") (class "Default")
      (node (ref "R48") (pin "2") (pinfunction "2_2") (pintype "passive"))
      (node (ref "X3") (pin "3") (pinfunction "KL_3") (pintype "passive"))
    )
    (net (code "21") (name "/DI3") (class "Default")
      (node (ref "R50") (pin "2") (pinfunction "2_2") (pintype "passive"))
      (node (ref "X3") (pin "4") (pinfunction "KL_4") (pintype "passive"))
    )
    (net (code "22") (name "/DI4") (class "Default")
      (node (ref "R52") (pin "2") (pinfunction "2_2") (pintype "passive"))
      (node (ref "X3") (pin "5") (pinfunction "KL_5") (pintype "passive"))
    )
    (net (code "23") (name "/DI5") (class "Default")
      (node (ref "R54") (pin "2") (pinfunction "2_2") (pintype "passive"))
      (node (ref "X3") (pin "6") (pinfunction "KL_6") (pintype "passive"))
    )
    (net (code "24") (name "/DI6") (class "Default")
      (node (ref "R56") (pin "2") (pinfunction "2_2") (pintype "passive"))
      (node (ref "X3") (pin "7") (pinfunction "KL_7") (pintype "passive"))
    )
    (net (code "25") (name "/DI7") (class "Default")
      (node (ref "R58") (pin "2") (pinfunction "2_2") (pintype "passive"))
      (node (ref "X3") (pin "8") (pinfunction "KL_8") (pintype "passive"))
    )
    (net (code "26") (name "/DI8") (class "Default")
      (node (ref "R60") (pin "2") (pinfunction "2_2") (pintype "passive"))
      (node (ref "X3") (pin "9") (pinfunction "KL_9") (pintype "passive"))
    )
    (net (code "27") (name "/DIM1_GND") (class "Default")
      (node (ref "C10") (pin "2") (pinfunction "2_2") (pintype "passive"))
      (node (ref "C9") (pin "2") (pinfunction "2_2") (pintype "passive"))
      (node (ref "D1") (pin "A") (pinfunction "A_A") (pintype "passive"))
      (node (ref "D20") (pin "A") (pinfunction "A_A") (pintype "passive"))
      (node (ref "D23") (pin "A") (pinfunction "A_A") (pintype "passive"))
      (node (ref "D42") (pin "A") (pinfunction "A_A") (pintype "passive"))
      (node (ref "IC1") (pin "4") (pinfunction "GND_4") (pintype "power_in"))
      (node (ref "OK3") (pin "3") (pinfunction "EMIT_3") (pintype "passive"))
      (node (ref "R29") (pin "1") (pinfunction "1_1") (pintype "passive"))
      (node (ref "R3") (pin "1") (pinfunction "1_1") (pintype "passive"))
      (node (ref "R6") (pin "1") (pinfunction "1_1") (pintype "passive"))
      (node (ref "T2") (pin "2") (pinfunction "S_2") (pintype "passive"))
    )
    (net (code "28") (name "/DIM1_VDD") (class "Default")
      (node (ref "D2") (pin "C") (pinfunction "C_C") (pintype "passive"))
      (node (ref "D21") (pin "C") (pinfunction "C_C") (pintype "passive"))
      (node (ref "D22") (pin "A") (pinfunction "A_A") (pintype "passive"))
      (node (ref "Q1") (pin "3") (pinfunction "S_3") (pintype "passive"))
      (node (ref "R1") (pin "2") (pinfunction "2_2") (pintype "passive"))
      (node (ref "R11") (pin "2") (pinfunction "2_2") (pintype "passive"))
    )
    (net (code "29") (name "/DIM2_GND") (class "Default")
      (node (ref "C3") (pin "2") (pinfunction "2_2") (pintype "passive"))
      (node (ref "C4") (pin "2") (pinfunction "2_2") (pintype "passive"))
      (node (ref "D24") (pin "A") (pinfunction "A_A") (pintype "passive"))
      (node (ref "D26") (pin "A") (pinfunction "A_A") (pintype "passive"))
      (node (ref "D29") (pin "A") (pinfunction "A_A") (pintype "passive"))
      (node (ref "D43") (pin "A") (pinfunction "A_A") (pintype "passive"))
      (node (ref "IC3") (pin "4") (pinfunction "GND_4") (pintype "power_in"))
      (node (ref "OK4") (pin "3") (pinfunction "EMIT_3") (pintype "passive"))
      (node (ref "R12") (pin "1") (pinfunction "1_1") (pintype "passive"))
      (node (ref "R31") (pin "1") (pinfunction "1_1") (pintype "passive"))
      (node (ref "R5") (pin "1") (pinfunction "1_1") (pintype "passive"))
      (node (ref "T4") (pin "2") (pinfunction "S_2") (pintype "passive"))
    )
    (net (code "30") (name "/DIM2_VDD") (class "Default")
      (node (ref "D25") (pin "C") (pinfunction "C_C") (pintype "passive"))
      (node (ref "D27") (pin "C") (pinfunction "C_C") (pintype "passive"))
      (node (ref "D28") (pin "A") (pinfunction "A_A") (pintype "passive"))
      (node (ref "Q2") (pin "3") (pinfunction "S_3") (pintype "passive"))
      (node (ref "R15") (pin "2") (pinfunction "2_2") (pintype "passive"))
      (node (ref "R4") (pin "2") (pinfunction "2_2") (pintype "passive"))
    )
    (net (code "31") (name "/DIM3_GND") (class "Default")
      (node (ref "C5") (pin "2") (pinfunction "2_2") (pintype "passive"))
      (node (ref "C7") (pin "2") (pinfunction "2_2") (pintype "passive"))
      (node (ref "D36") (pin "A") (pinfunction "A_A") (pintype "passive"))
      (node (ref "D38") (pin "A") (pinfunction "A_A") (pintype "passive"))
      (node (ref "D41") (pin "A") (pinfunction "A_A") (pintype "passive"))
      (node (ref "D44") (pin "A") (pinfunction "A_A") (pintype "passive"))
      (node (ref "IC5") (pin "4") (pinfunction "GND_4") (pintype "power_in"))
      (node (ref "OK5") (pin "3") (pinfunction "EMIT_3") (pintype "passive"))
      (node (ref "R23") (pin "1") (pinfunction "1_1") (pintype "passive"))
      (node (ref "R25") (pin "1") (pinfunction "1_1") (pintype "passive"))
      (node (ref "R33") (pin "1") (pinfunction "1_1") (pintype "passive"))
      (node (ref "T8") (pin "2") (pinfunction "S_2") (pintype "passive"))
    )
    (net (code "32") (name "/DIM3_VDD") (class "Default")
      (node (ref "D37") (pin "C") (pinfunction "C_C") (pintype "passive"))
      (node (ref "D39") (pin "C") (pinfunction "C_C") (pintype "passive"))
      (node (ref "D40") (pin "A") (pinfunction "A_A") (pintype "passive"))
      (node (ref "Q5") (pin "3") (pinfunction "S_3") (pintype "passive"))
      (node (ref "R22") (pin "2") (pinfunction "2_2") (pintype "passive"))
      (node (ref "R28") (pin "2") (pinfunction "2_2") (pintype "passive"))
    )
    (net (code "33") (name "/DIM4_GND") (class "Default")
      (node (ref "C11") (pin "2") (pinfunction "2_2") (pintype "passive"))
      (node (ref "C8") (pin "2") (pinfunction "2_2") (pintype "passive"))
      (node (ref "D30") (pin "A") (pinfunction "A_A") (pintype "passive"))
      (node (ref "D32") (pin "A") (pinfunction "A_A") (pintype "passive"))
      (node (ref "D35") (pin "A") (pinfunction "A_A") (pintype "passive"))
      (node (ref "D45") (pin "A") (pinfunction "A_A") (pintype "passive"))
      (node (ref "IC7") (pin "4") (pinfunction "GND_4") (pintype "power_in"))
      (node (ref "OK6") (pin "3") (pinfunction "EMIT_3") (pintype "passive"))
      (node (ref "R17") (pin "1") (pinfunction "1_1") (pintype "passive"))
      (node (ref "R18") (pin "1") (pinfunction "1_1") (pintype "passive"))
      (node (ref "R35") (pin "1") (pinfunction "1_1") (pintype "passive"))
      (node (ref "T6") (pin "2") (pinfunction "S_2") (pintype "passive"))
    )
    (net (code "34") (name "/DIM4_VDD") (class "Default")
      (node (ref "D31") (pin "C") (pinfunction "C_C") (pintype "passive"))
      (node (ref "D33") (pin "C") (pinfunction "C_C") (pintype "passive"))
      (node (ref "D34") (pin "A") (pinfunction "A_A") (pintype "passive"))
      (node (ref "Q4") (pin "3") (pinfunction "S_3") (pintype "passive"))
      (node (ref "R16") (pin "2") (pinfunction "2_2") (pintype "passive"))
      (node (ref "R21") (pin "2") (pinfunction "2_2") (pintype "passive"))
    )
    (net (code "35") (name "/DIMMER1") (class "Default")
      (node (ref "D20") (pin "C") (pinfunction "C_C") (pintype "passive"))
      (node (ref "D21") (pin "A") (pinfunction "A_A") (pintype "passive"))
      (node (ref "R10") (pin "2") (pinfunction "2_2") (pintype "passive"))
      (node (ref "X2") (pin "2") (pinfunction "KL_2") (pintype "passive"))
    )
    (net (code "36") (name "/DIMMER2") (class "Default")
      (node (ref "D26") (pin "C") (pinfunction "C_C") (pintype "passive"))
      (node (ref "D27") (pin "A") (pinfunction "A_A") (pintype "passive"))
      (node (ref "R13") (pin "2") (pinfunction "2_2") (pintype "passive"))
      (node (ref "X2") (pin "4") (pinfunction "KL_4") (pintype "passive"))
    )
    (net (code "37") (name "/DIMMER3") (class "Default")
      (node (ref "D38") (pin "C") (pinfunction "C_C") (pintype "passive"))
      (node (ref "D39") (pin "A") (pinfunction "A_A") (pintype "passive"))
      (node (ref "R26") (pin "2") (pinfunction "2_2") (pintype "passive"))
      (node (ref "X2") (pin "6") (pinfunction "KL_6") (pintype "passive"))
    )
    (net (code "38") (name "/DIMMER4") (class "Default")
      (node (ref "D32") (pin "C") (pinfunction "C_C") (pintype "passive"))
      (node (ref "D33") (pin "A") (pinfunction "A_A") (pintype "passive"))
      (node (ref "R19") (pin "2") (pinfunction "2_2") (pintype "passive"))
      (node (ref "X2") (pin "8") (pinfunction "KL_8") (pintype "passive"))
    )
    (net (code "39") (name "/GATE_DIM1") (class "Default")
      (node (ref "Q1") (pin "1") (pinfunction "G_1") (pintype "passive"))
      (node (ref "R9") (pin "1") (pinfunction "1_1") (pintype "passive"))
      (node (ref "T2") (pin "3") (pinfunction "D_3") (pintype "passive"))
    )
    (net (code "40") (name "/GATE_DIM2") (class "Default")
      (node (ref "Q2") (pin "1") (pinfunction "G_1") (pintype "passive"))
      (node (ref "R14") (pin "1") (pinfunction "1_1") (pintype "passive"))
      (node (ref "T4") (pin "3") (pinfunction "D_3") (pintype "passive"))
    )
    (net (code "41") (name "/GATE_DIM3") (class "Default")
      (node (ref "Q5") (pin "1") (pinfunction "G_1") (pintype "passive"))
      (node (ref "R27") (pin "1") (pinfunction "1_1") (pintype "passive"))
      (node (ref "T8") (pin "3") (pinfunction "D_3") (pintype "passive"))
    )
    (net (code "42") (name "/GATE_DIM4") (class "Default")
      (node (ref "Q4") (pin "1") (pinfunction "G_1") (pintype "passive"))
      (node (ref "R20") (pin "1") (pinfunction "1_1") (pintype "passive"))
      (node (ref "T6") (pin "3") (pinfunction "D_3") (pintype "passive"))
    )
    (net (code "43") (name "/IN1") (class "Default")
      (node (ref "IC2") (pin "6") (pinfunction "PA0/ADC_IN0_6") (pintype "bidirectional"))
      (node (ref "OK1") (pin "16") (pinfunction "COL_16") (pintype "passive"))
      (node (ref "R7") (pin "1") (pinfunction "1_1") (pintype "passive"))
    )
    (net (code "44") (name "/IN2") (class "Default")
      (node (ref "IC2") (pin "7") (pinfunction "PA1/TIM2_CH2/ADC_IN1_7") (pintype "bidirectional"))
      (node (ref "OK1") (pin "14") (pinfunction "COL_14") (pintype "passive"))
      (node (ref "R47") (pin "1") (pinfunction "1_1") (pintype "passive"))
    )
    (net (code "45") (name "/IN3") (class "Default")
      (node (ref "IC2") (pin "8") (pinfunction "PA2/USART2_TX/TIM2_CH3/ADC_IN2_8") (pintype "bidirectional"))
      (node (ref "OK1") (pin "12") (pinfunction "COL_12") (pintype "passive"))
      (node (ref "R49") (pin "1") (pinfunction "1_1") (pintype "passive"))
    )
    (net (code "46") (name "/IN4") (class "Default")
      (node (ref "IC2") (pin "9") (pinfunction "PA3/USART2_RX/TIM2_CH4/ADC_IN3_9") (pintype "bidirectional"))
      (node (ref "OK1") (pin "10") (pinfunction "COL_10") (pintype "passive"))
      (node (ref "R51") (pin "1") (pinfunction "1_1") (pintype "passive"))
    )
    (net (code "47") (name "/IN5") (class "Default")
      (node (ref "IC2") (pin "10") (pinfunction "PA4/SPI1_NSS/TIM14_CH1/ADC_IN4_10") (pintype "bidirectional"))
      (node (ref "OK2") (pin "16") (pinfunction "COL_16") (pintype "passive"))
      (node (ref "R53") (pin "1") (pinfunction "1_1") (pintype "passive"))
    )
    (net (code "48") (name "/IN6") (class "Default")
      (node (ref "IC2") (pin "11") (pinfunction "PA5/SPI1_SCK/ADC_IN5_11") (pintype "bidirectional"))
      (node (ref "OK2") (pin "14") (pinfunction "COL_14") (pintype "passive"))
      (node (ref "R55") (pin "1") (pinfunction "1_1") (pintype "passive"))
    )
    (net (code "49") (name "/IN7") (class "Default")
      (node (ref "IC2") (pin "12") (pinfunction "PA6/SPI1_MISO/TIM3_CH1/ADC_IN6_12") (pintype "bidirectional"))
      (node (ref "OK2") (pin "12") (pinfunction "COL_12") (pintype "passive"))
      (node (ref "R57") (pin "1") (pinfunction "1_1") (pintype "passive"))
    )
    (net (code "50") (name "/IN8") (class "Default")
      (node (ref "IC2") (pin "13") (pinfunction "PA7/SPI1_MOSI/TIM3_CH2/ADC_IN7_13") (pintype "bidirectional"))
      (node (ref "OK2") (pin "10") (pinfunction "COL_10") (pintype "passive"))
      (node (ref "R59") (pin "1") (pinfunction "1_1") (pintype "passive"))
    )
    (net (code "51") (name "/PHASE1") (class "Default")
      (node (ref "D1") (pin "C") (pinfunction "C_C") (pintype "passive"))
      (node (ref "D2") (pin "A") (pinfunction "A_A") (pintype "passive"))
      (node (ref "R10") (pin "1") (pinfunction "1_1") (pintype "passive"))
      (node (ref "X2") (pin "1") (pinfunction "KL_1") (pintype "passive"))
    )
    (net (code "52") (name "/PHASE2") (class "Default")
      (node (ref "D24") (pin "C") (pinfunction "C_C") (pintype "passive"))
      (node (ref "D25") (pin "A") (pinfunction "A_A") (pintype "passive"))
      (node (ref "R13") (pin "1") (pinfunction "1_1") (pintype "passive"))
      (node (ref "X2") (pin "3") (pinfunction "KL_3") (pintype "passive"))
    )
    (net (code "53") (name "/PHASE3") (class "Default")
      (node (ref "D36") (pin "C") (pinfunction "C_C") (pintype "passive"))
      (node (ref "D37") (pin "A") (pinfunction "A_A") (pintype "passive"))
      (node (ref "R26") (pin "1") (pinfunction "1_1") (pintype "passive"))
      (node (ref "X2") (pin "5") (pinfunction "KL_5") (pintype "passive"))
    )
    (net (code "54") (name "/PHASE4") (class "Default")
      (node (ref "D30") (pin "C") (pinfunction "C_C") (pintype "passive"))
      (node (ref "D31") (pin "A") (pinfunction "A_A") (pintype "passive"))
      (node (ref "R19") (pin "1") (pinfunction "1_1") (pintype "passive"))
      (node (ref "X2") (pin "7") (pinfunction "KL_7") (pintype "passive"))
    )
    (net (code "55") (name "/PWM1") (class "Default")
      (node (ref "IC2") (pin "28") (pinfunction "PB5/SPI1_MOSI/TIM3_CH1_28") (pintype "bidirectional"))
      (node (ref "T9") (pin "1") (pinfunction "G_1") (pintype "passive"))
    )
    (net (code "56") (name "/PWM2") (class "Default")
      (node (ref "IC2") (pin "27") (pinfunction "PB4/SPI1_MISO/TIM3_CH2_27") (pintype "bidirectional"))
      (node (ref "T10") (pin "1") (pinfunction "G_1") (pintype "passive"))
    )
    (net (code "57") (name "/PWM3") (class "Default")
      (node (ref "IC2") (pin "14") (pinfunction "PB0/TIM3_CH3/ADC_IN8_14") (pintype "bidirectional"))
      (node (ref "T11") (pin "1") (pinfunction "G_1") (pintype "passive"))
    )
    (net (code "58") (name "/PWM4") (class "Default")
      (node (ref "IC2") (pin "15") (pinfunction "PB1/TIM3_CH4/TIM14_CH1/ADC_IN9_15") (pintype "bidirectional"))
      (node (ref "T12") (pin "1") (pinfunction "G_1") (pintype "passive"))
    )
    (net (code "59") (name "/PWM_DIM1") (class "Default")
      (node (ref "IC1") (pin "5") (pinfunction "MOSI/PB0_5") (pintype "bidirectional"))
      (node (ref "T2") (pin "1") (pinfunction "G_1") (pintype "passive"))
    )
    (net (code "60") (name "/PWM_DIM2") (class "Default")
      (node (ref "IC3") (pin "5") (pinfunction "MOSI/PB0_5") (pintype "bidirectional"))
      (node (ref "T4") (pin "1") (pinfunction "G_1") (pintype "passive"))
    )
    (net (code "61") (name "/PWM_DIM3") (class "Default")
      (node (ref "IC5") (pin "5") (pinfunction "MOSI/PB0_5") (pintype "bidirectional"))
      (node (ref "T8") (pin "1") (pinfunction "G_1") (pintype "passive"))
    )
    (net (code "62") (name "/PWM_DIM4") (class "Default")
      (node (ref "IC7") (pin "5") (pinfunction "MOSI/PB0_5") (pintype "bidirectional"))
      (node (ref "T6") (pin "1") (pinfunction "G_1") (pintype "passive"))
    )
    (net (code "63") (name "/SWCLK") (class "Default")
      (node (ref "IC2") (pin "24") (pinfunction "PA14/USART2_TX/SWCLK_24") (pintype "bidirectional"))
      (node (ref "K5") (pin "2") (pinfunction "2_2") (pintype "passive"))
    )
    (net (code "64") (name "/SWDIO") (class "Default")
      (node (ref "IC2") (pin "23") (pinfunction "PA13/SWDIO/USB_NOE_23") (pintype "bidirectional"))
      (node (ref "K5") (pin "4") (pinfunction "4_4") (pintype "passive"))
    )
    (net (code "65") (name "/UC_BOOT") (class "Default")
      (node (ref "IC2") (pin "31") (pinfunction "BOOT0_31") (pintype "bidirectional"))
      (node (ref "R24") (pin "2") (pinfunction "2_2") (pintype "passive"))
    )
    (net (code "66") (name "/UC_NRST") (class "Default")
      (node (ref "IC2") (pin "4") (pinfunction "NRST_4") (pintype "bidirectional"))
      (node (ref "K5") (pin "5") (pinfunction "5_5") (pintype "passive"))
      (node (ref "R2") (pin "1") (pinfunction "1_1") (pintype "passive"))
    )
    (net (code "67") (name "GND") (class "Default")
      (node (ref "C1") (pin "2") (pinfunction "2_2") (pintype "passive"))
      (node (ref "C13") (pin "2") (pinfunction "2_2") (pintype "passive"))
      (node (ref "C2") (pin "1") (pinfunction "1_1") (pintype "passive"))
      (node (ref "C27") (pin "2") (pinfunction "2_2") (pintype "passive"))
      (node (ref "C28") (pin "2") (pinfunction "2_2") (pintype "passive"))
      (node (ref "C29") (pin "2") (pinfunction "2_2") (pintype "passive"))
      (node (ref "D11") (pin "A") (pinfunction "A_A") (pintype "passive"))
      (node (ref "D13") (pin "A") (pinfunction "A_A") (pintype "passive"))
      (node (ref "D15") (pin "A") (pinfunction "A_A") (pintype "passive"))
      (node (ref "D17") (pin "A") (pinfunction "A_A") (pintype "passive"))
      (node (ref "D19") (pin "A") (pinfunction "A_A") (pintype "passive"))
      (node (ref "D4") (pin "A") (pinfunction "A_A") (pintype "passive"))
      (node (ref "D5") (pin "A") (pinfunction "A_A") (pintype "passive"))
      (node (ref "D7") (pin "A") (pinfunction "A_A") (pintype "passive"))
      (node (ref "D9") (pin "A") (pinfunction "A_A") (pintype "passive"))
      (node (ref "IC2") (pin "16") (pinfunction "VSS_16") (pintype "power_in"))
      (node (ref "IC2") (pin "32") (pinfunction "VSS_32") (pintype "power_in"))
      (node (ref "K5") (pin "3") (pinfunction "3_3") (pintype "passive"))
      (node (ref "OK1") (pin "11") (pinfunction "EMIT_11") (pintype "passive"))
      (node (ref "OK1") (pin "13") (pinfunction "EMIT_13") (pintype "passive"))
      (node (ref "OK1") (pin "15") (pinfunction "EMIT_15") (pintype "passive"))
      (node (ref "OK1") (pin "2") (pinfunction "C_2") (pintype "passive"))
      (node (ref "OK1") (pin "4") (pinfunction "C_4") (pintype "passive"))
      (node (ref "OK1") (pin "6") (pinfunction "C_6") (pintype "passive"))
      (node (ref "OK1") (pin "8") (pinfunction "C_8") (pintype "passive"))
      (node (ref "OK1") (pin "9") (pinfunction "EMIT_9") (pintype "passive"))
      (node (ref "OK2") (pin "11") (pinfunction "EMIT_11") (pintype "passive"))
      (node (ref "OK2") (pin "13") (pinfunction "EMIT_13") (pintype "passive"))
      (node (ref "OK2") (pin "15") (pinfunction "EMIT_15") (pintype "passive"))
      (node (ref "OK2") (pin "2") (pinfunction "C_2") (pintype "passive"))
      (node (ref "OK2") (pin "4") (pinfunction "C_4") (pintype "passive"))
      (node (ref "OK2") (pin "6") (pinfunction "C_6") (pintype "passive"))
      (node (ref "OK2") (pin "8") (pinfunction "C_8") (pintype "passive"))
      (node (ref "OK2") (pin "9") (pinfunction "EMIT_9") (pintype "passive"))
      (node (ref "R24") (pin "1") (pinfunction "1_1") (pintype "passive"))
      (node (ref "R45") (pin "1") (pinfunction "1_1") (pintype "passive"))
      (node (ref "T10") (pin "2") (pinfunction "S_2") (pintype "passive"))
      (node (ref "T11") (pin "2") (pinfunction "S_2") (pintype "passive"))
      (node (ref "T12") (pin "2") (pinfunction "S_2") (pintype "passive"))
      (node (ref "T9") (pin "2") (pinfunction "S_2") (pintype "passive"))
      (node (ref "U$1") (pin "2") (pinfunction "VSS_2") (pintype "passive"))
      (node (ref "U1") (pin "1") (pinfunction "ADJ_1") (pintype "bidirectional"))
      (node (ref "X1") (pin "10") (pinfunction "KL_10") (pintype "passive"))
      (node (ref "X1") (pin "3") (pinfunction "KL_3") (pintype "passive"))
      (node (ref "X1") (pin "4") (pinfunction "KL_4") (pintype "passive"))
      (node (ref "X1") (pin "5") (pinfunction "KL_5") (pintype "passive"))
      (node (ref "X1") (pin "6") (pinfunction "KL_6") (pintype "passive"))
      (node (ref "X1") (pin "9") (pinfunction "KL_9") (pintype "passive"))
      (node (ref "X3") (pin "1") (pinfunction "KL_1") (pintype "passive"))
      (node (ref "X3") (pin "10") (pinfunction "KL_10") (pintype "passive"))
    )
    (net (code "68") (name "Net-(D3-PadC)") (class "Default")
      (node (ref "D3") (pin "C") (pinfunction "C_C") (pintype "passive"))
      (node (ref "R8") (pin "1") (pinfunction "1_1") (pintype "passive"))
    )
    (net (code "69") (name "Net-(D6-PadC)") (class "Default")
      (node (ref "D6") (pin "C") (pinfunction "C_C") (pintype "passive"))
      (node (ref "R48") (pin "1") (pinfunction "1_1") (pintype "passive"))
    )
    (net (code "70") (name "Net-(D8-PadC)") (class "Default")
      (node (ref "D8") (pin "C") (pinfunction "C_C") (pintype "passive"))
      (node (ref "R50") (pin "1") (pinfunction "1_1") (pintype "passive"))
    )
    (net (code "71") (name "Net-(D10-PadC)") (class "Default")
      (node (ref "D10") (pin "C") (pinfunction "C_C") (pintype "passive"))
      (node (ref "R52") (pin "1") (pinfunction "1_1") (pintype "passive"))
    )
    (net (code "72") (name "Net-(D12-PadC)") (class "Default")
      (node (ref "D12") (pin "C") (pinfunction "C_C") (pintype "passive"))
      (node (ref "R54") (pin "1") (pinfunction "1_1") (pintype "passive"))
    )
    (net (code "73") (name "Net-(D14-PadC)") (class "Default")
      (node (ref "D14") (pin "C") (pinfunction "C_C") (pintype "passive"))
      (node (ref "R56") (pin "1") (pinfunction "1_1") (pintype "passive"))
    )
    (net (code "74") (name "Net-(D16-PadC)") (class "Default")
      (node (ref "D16") (pin "C") (pinfunction "C_C") (pintype "passive"))
      (node (ref "R58") (pin "1") (pinfunction "1_1") (pintype "passive"))
    )
    (net (code "75") (name "Net-(D18-PadC)") (class "Default")
      (node (ref "D18") (pin "C") (pinfunction "C_C") (pintype "passive"))
      (node (ref "R60") (pin "1") (pinfunction "1_1") (pintype "passive"))
    )
    (net (code "76") (name "Net-(IC1-RST{slash}PB5)") (class "Default")
      (node (ref "IC1") (pin "1") (pinfunction "RST/PB5_1") (pintype "bidirectional"))
      (node (ref "R29") (pin "2") (pinfunction "2_2") (pintype "passive"))
    )
    (net (code "77") (name "Net-(IC1-VCC)") (class "Default")
      (node (ref "C9") (pin "1") (pinfunction "1_1") (pintype "passive"))
      (node (ref "D42") (pin "C") (pinfunction "C_C") (pintype "passive"))
      (node (ref "IC1") (pin "8") (pinfunction "VCC_8") (pintype "power_in"))
      (node (ref "R30") (pin "2") (pinfunction "2_2") (pintype "passive"))
      (node (ref "R37") (pin "1") (pinfunction "1_1") (pintype "passive"))
    )
    (net (code "78") (name "Net-(IC3-RST{slash}PB5)") (class "Default")
      (node (ref "IC3") (pin "1") (pinfunction "RST/PB5_1") (pintype "bidirectional"))
      (node (ref "R31") (pin "2") (pinfunction "2_2") (pintype "passive"))
    )
    (net (code "79") (name "Net-(IC3-VCC)") (class "Default")
      (node (ref "C3") (pin "1") (pinfunction "1_1") (pintype "passive"))
      (node (ref "D43") (pin "C") (pinfunction "C_C") (pintype "passive"))
      (node (ref "IC3") (pin "8") (pinfunction "VCC_8") (pintype "power_in"))
      (node (ref "R32") (pin "2") (pinfunction "2_2") (pintype "passive"))
      (node (ref "R38") (pin "1") (pinfunction "1_1") (pintype "passive"))
    )
    (net (code "80") (name "Net-(IC5-RST{slash}PB5)") (class "Default")
      (node (ref "IC5") (pin "1") (pinfunction "RST/PB5_1") (pintype "bidirectional"))
      (node (ref "R33") (pin "2") (pinfunction "2_2") (pintype "passive"))
    )
    (net (code "81") (name "Net-(IC5-VCC)") (class "Default")
      (node (ref "C7") (pin "1") (pinfunction "1_1") (pintype "passive"))
      (node (ref "D44") (pin "C") (pinfunction "C_C") (pintype "passive"))
      (node (ref "IC5") (pin "8") (pinfunction "VCC_8") (pintype "power_in"))
      (node (ref "R34") (pin "2") (pinfunction "2_2") (pintype "passive"))
      (node (ref "R39") (pin "1") (pinfunction "1_1") (pintype "passive"))
    )
    (net (code "82") (name "Net-(IC7-RST{slash}PB5)") (class "Default")
      (node (ref "IC7") (pin "1") (pinfunction "RST/PB5_1") (pintype "bidirectional"))
      (node (ref "R35") (pin "2") (pinfunction "2_2") (pintype "passive"))
    )
    (net (code "83") (name "Net-(IC7-VCC)") (class "Default")
      (node (ref "C8") (pin "1") (pinfunction "1_1") (pintype "passive"))
      (node (ref "D45") (pin "C") (pinfunction "C_C") (pintype "passive"))
      (node (ref "IC7") (pin "8") (pinfunction "VCC_8") (pintype "power_in"))
      (node (ref "R36") (pin "2") (pinfunction "2_2") (pintype "passive"))
      (node (ref "R40") (pin "1") (pinfunction "1_1") (pintype "passive"))
    )
    (net (code "84") (name "Net-(OK1A-A)") (class "Default")
      (node (ref "D3") (pin "A") (pinfunction "A_A") (pintype "passive"))
      (node (ref "D4") (pin "C") (pinfunction "C_C") (pintype "passive"))
      (node (ref "OK1") (pin "1") (pinfunction "A_1") (pintype "passive"))
    )
    (net (code "85") (name "Net-(OK1B-A)") (class "Default")
      (node (ref "D6") (pin "A") (pinfunction "A_A") (pintype "passive"))
      (node (ref "D7") (pin "C") (pinfunction "C_C") (pintype "passive"))
      (node (ref "OK1") (pin "3") (pinfunction "A_3") (pintype "passive"))
    )
    (net (code "86") (name "Net-(OK1C-A)") (class "Default")
      (node (ref "D8") (pin "A") (pinfunction "A_A") (pintype "passive"))
      (node (ref "D9") (pin "C") (pinfunction "C_C") (pintype "passive"))
      (node (ref "OK1") (pin "5") (pinfunction "A_5") (pintype "passive"))
    )
    (net (code "87") (name "Net-(OK1D-A)") (class "Default")
      (node (ref "D10") (pin "A") (pinfunction "A_A") (pintype "passive"))
      (node (ref "D11") (pin "C") (pinfunction "C_C") (pintype "passive"))
      (node (ref "OK1") (pin "7") (pinfunction "A_7") (pintype "passive"))
    )
    (net (code "88") (name "Net-(OK2A-A)") (class "Default")
      (node (ref "D12") (pin "A") (pinfunction "A_A") (pintype "passive"))
      (node (ref "D13") (pin "C") (pinfunction "C_C") (pintype "passive"))
      (node (ref "OK2") (pin "1") (pinfunction "A_1") (pintype "passive"))
    )
    (net (code "89") (name "Net-(OK2B-A)") (class "Default")
      (node (ref "D14") (pin "A") (pinfunction "A_A") (pintype "passive"))
      (node (ref "D15") (pin "C") (pinfunction "C_C") (pintype "passive"))
      (node (ref "OK2") (pin "3") (pinfunction "A_3") (pintype "passive"))
    )
    (net (code "90") (name "Net-(OK2C-A)") (class "Default")
      (node (ref "D16") (pin "A") (pinfunction "A_A") (pintype "passive"))
      (node (ref "D17") (pin "C") (pinfunction "C_C") (pintype "passive"))
      (node (ref "OK2") (pin "5") (pinfunction "A_5") (pintype "passive"))
    )
    (net (code "91") (name "Net-(OK2D-A)") (class "Default")
      (node (ref "D18") (pin "A") (pinfunction "A_A") (pintype "passive"))
      (node (ref "D19") (pin "C") (pinfunction "C_C") (pintype "passive"))
      (node (ref "OK2") (pin "7") (pinfunction "A_7") (pintype "passive"))
    )
    (net (code "92") (name "Net-(OK3-A)") (class "Default")
      (node (ref "OK3") (pin "1") (pinfunction "A_1") (pintype "passive"))
      (node (ref "R41") (pin "1") (pinfunction "1_1") (pintype "passive"))
    )
    (net (code "93") (name "Net-(OK3-C)") (class "Default")
      (node (ref "OK3") (pin "2") (pinfunction "C_2") (pintype "passive"))
      (node (ref "T9") (pin "3") (pinfunction "D_3") (pintype "passive"))
    )
    (net (code "94") (name "Net-(OK4-A)") (class "Default")
      (node (ref "OK4") (pin "1") (pinfunction "A_1") (pintype "passive"))
      (node (ref "R42") (pin "1") (pinfunction "1_1") (pintype "passive"))
    )
    (net (code "95") (name "Net-(OK4-C)") (class "Default")
      (node (ref "OK4") (pin "2") (pinfunction "C_2") (pintype "passive"))
      (node (ref "T10") (pin "3") (pinfunction "D_3") (pintype "passive"))
    )
    (net (code "96") (name "Net-(OK5-A)") (class "Default")
      (node (ref "OK5") (pin "1") (pinfunction "A_1") (pintype "passive"))
      (node (ref "R43") (pin "1") (pinfunction "1_1") (pintype "passive"))
    )
    (net (code "97") (name "Net-(OK5-C)") (class "Default")
      (node (ref "OK5") (pin "2") (pinfunction "C_2") (pintype "passive"))
      (node (ref "T11") (pin "3") (pinfunction "D_3") (pintype "passive"))
    )
    (net (code "98") (name "Net-(OK6-A)") (class "Default")
      (node (ref "OK6") (pin "1") (pinfunction "A_1") (pintype "passive"))
      (node (ref "R44") (pin "1") (pinfunction "1_1") (pintype "passive"))
    )
    (net (code "99") (name "Net-(OK6-C)") (class "Default")
      (node (ref "OK6") (pin "2") (pinfunction "C_2") (pintype "passive"))
      (node (ref "T12") (pin "3") (pinfunction "D_3") (pintype "passive"))
    )
    (net (code "100") (name "Net-(T1-D)") (class "Default")
      (node (ref "D22") (pin "C") (pinfunction "C_C") (pintype "passive"))
      (node (ref "T1") (pin "1") (pinfunction "D_1") (pintype "passive"))
    )
    (net (code "101") (name "Net-(T1-G)") (class "Default")
      (node (ref "D23") (pin "C") (pinfunction "C_C") (pintype "passive"))
      (node (ref "R11") (pin "1") (pinfunction "1_1") (pintype "passive"))
      (node (ref "T1") (pin "3") (pinfunction "G_3") (pintype "passive"))
    )
    (net (code "102") (name "Net-(T1-S)") (class "Default")
      (node (ref "C10") (pin "1") (pinfunction "1_1") (pintype "passive"))
      (node (ref "R37") (pin "2") (pinfunction "2_2") (pintype "passive"))
      (node (ref "R9") (pin "2") (pinfunction "2_2") (pintype "passive"))
      (node (ref "T1") (pin "2") (pinfunction "S_2") (pintype "passive"))
    )
    (net (code "103") (name "Net-(T3-D)") (class "Default")
      (node (ref "D28") (pin "C") (pinfunction "C_C") (pintype "passive"))
      (node (ref "T3") (pin "1") (pinfunction "D_1") (pintype "passive"))
    )
    (net (code "104") (name "Net-(T3-G)") (class "Default")
      (node (ref "D29") (pin "C") (pinfunction "C_C") (pintype "passive"))
      (node (ref "R15") (pin "1") (pinfunction "1_1") (pintype "passive"))
      (node (ref "T3") (pin "3") (pinfunction "G_3") (pintype "passive"))
    )
    (net (code "105") (name "Net-(T3-S)") (class "Default")
      (node (ref "C4") (pin "1") (pinfunction "1_1") (pintype "passive"))
      (node (ref "R14") (pin "2") (pinfunction "2_2") (pintype "passive"))
      (node (ref "R38") (pin "2") (pinfunction "2_2") (pintype "passive"))
      (node (ref "T3") (pin "2") (pinfunction "S_2") (pintype "passive"))
    )
    (net (code "106") (name "Net-(T5-D)") (class "Default")
      (node (ref "D34") (pin "C") (pinfunction "C_C") (pintype "passive"))
      (node (ref "T5") (pin "1") (pinfunction "D_1") (pintype "passive"))
    )
    (net (code "107") (name "Net-(T5-G)") (class "Default")
      (node (ref "D35") (pin "C") (pinfunction "C_C") (pintype "passive"))
      (node (ref "R21") (pin "1") (pinfunction "1_1") (pintype "passive"))
      (node (ref "T5") (pin "3") (pinfunction "G_3") (pintype "passive"))
    )
    (net (code "108") (name "Net-(T5-S)") (class "Default")
      (node (ref "C11") (pin "1") (pinfunction "1_1") (pintype "passive"))
      (node (ref "R20") (pin "2") (pinfunction "2_2") (pintype "passive"))
      (node (ref "R40") (pin "2") (pinfunction "2_2") (pintype "passive"))
      (node (ref "T5") (pin "2") (pinfunction "S_2") (pintype "passive"))
    )
    (net (code "109") (name "Net-(T7-D)") (class "Default")
      (node (ref "D40") (pin "C") (pinfunction "C_C") (pintype "passive"))
      (node (ref "T7") (pin "1") (pinfunction "D_1") (pintype "passive"))
    )
    (net (code "110") (name "Net-(T7-G)") (class "Default")
      (node (ref "D41") (pin "C") (pinfunction "C_C") (pintype "passive"))
      (node (ref "R28") (pin "1") (pinfunction "1_1") (pintype "passive"))
      (node (ref "T7") (pin "3") (pinfunction "G_3") (pintype "passive"))
    )
    (net (code "111") (name "Net-(T7-S)") (class "Default")
      (node (ref "C5") (pin "1") (pinfunction "1_1") (pintype "passive"))
      (node (ref "R27") (pin "2") (pinfunction "2_2") (pintype "passive"))
      (node (ref "R39") (pin "2") (pinfunction "2_2") (pintype "passive"))
      (node (ref "T7") (pin "2") (pinfunction "S_2") (pintype "passive"))
    )
    (net (code "112") (name "Net-(U$1-RS)") (class "Default")
      (node (ref "R45") (pin "2") (pinfunction "2_2") (pintype "passive"))
      (node (ref "U$1") (pin "8") (pinfunction "RS_8") (pintype "input"))
    )
    (net (code "113") (name "Net-(U1-IN)") (class "Default")
      (node (ref "C13") (pin "1") (pinfunction "1_1") (pintype "passive"))
      (node (ref "D5") (pin "C") (pinfunction "C_C") (pintype "passive"))
      (node (ref "F1") (pin "2") (pinfunction "2_2") (pintype "passive"))
      (node (ref "U1") (pin "2") (pinfunction "IN_2") (pintype "bidirectional"))
    )
    (net (code "114") (name "Net-(X2B-KL)") (class "Default")
      (node (ref "X2") (pin "10") (pinfunction "KL_10") (pintype "passive"))
      (node (ref "X2") (pin "9") (pinfunction "KL_9") (pintype "passive"))
    )
    (net (code "115") (name "unconnected-(IC1-SCK{slash}PB2-Pad7)") (class "Default")
      (node (ref "IC1") (pin "7") (pinfunction "SCK/PB2_7") (pintype "bidirectional"))
    )
    (net (code "116") (name "unconnected-(IC2-PA8{slash}TIM1_CH1-Pad18)") (class "Default")
      (node (ref "IC2") (pin "18") (pinfunction "PA8/TIM1_CH1_18") (pintype "bidirectional"))
    )
    (net (code "117") (name "unconnected-(IC2-PA9{slash}USART1_TX{slash}TIM1_CH2{slash}I2C1_SCL-Pad19)") (class "Default")
      (node (ref "IC2") (pin "19") (pinfunction "PA9/USART1_TX/TIM1_CH2/I2C1_SCL_19") (pintype "bidirectional"))
    )
    (net (code "118") (name "unconnected-(IC2-PA10{slash}USART_RX{slash}TIM1_CH3{slash}I2C1_SDA-Pad20)") (class "Default")
      (node (ref "IC2") (pin "20") (pinfunction "PA10/USART_RX/TIM1_CH3/I2C1_SDA_20") (pintype "bidirectional"))
    )
    (net (code "119") (name "unconnected-(IC2-PA15{slash}USART2_RX{slash}SPI1_NSS-Pad25)") (class "Default")
      (node (ref "IC2") (pin "25") (pinfunction "PA15/USART2_RX/SPI1_NSS_25") (pintype "bidirectional"))
    )
    (net (code "120") (name "unconnected-(IC2-PB3{slash}SPI1_SCK{slash}TIM2_CH2-Pad26)") (class "Default")
      (node (ref "IC2") (pin "26") (pinfunction "PB3/SPI1_SCK/TIM2_CH2_26") (pintype "bidirectional"))
    )
    (net (code "121") (name "unconnected-(IC2-PB6{slash}I2C1_SCL{slash}USART1_TX-Pad29)") (class "Default")
      (node (ref "IC2") (pin "29") (pinfunction "PB6/I2C1_SCL/USART1_TX_29") (pintype "bidirectional"))
    )
    (net (code "122") (name "unconnected-(IC2-PB7{slash}I2C1_SDA{slash}USART1_RX-Pad30)") (class "Default")
      (node (ref "IC2") (pin "30") (pinfunction "PB7/I2C1_SDA/USART1_RX_30") (pintype "bidirectional"))
    )
    (net (code "123") (name "unconnected-(IC2-PF0_OSC_IN-Pad2)") (class "Default")
      (node (ref "IC2") (pin "2") (pinfunction "PF0_OSC_IN_2") (pintype "bidirectional"))
    )
    (net (code "124") (name "unconnected-(IC2-PF1_OSC_OUT-Pad3)") (class "Default")
      (node (ref "IC2") (pin "3") (pinfunction "PF1_OSC_OUT_3") (pintype "bidirectional"))
    )
    (net (code "125") (name "unconnected-(IC3-SCK{slash}PB2-Pad7)") (class "Default")
      (node (ref "IC3") (pin "7") (pinfunction "SCK/PB2_7") (pintype "bidirectional"))
    )
    (net (code "126") (name "unconnected-(IC5-SCK{slash}PB2-Pad7)") (class "Default")
      (node (ref "IC5") (pin "7") (pinfunction "SCK/PB2_7") (pintype "bidirectional"))
    )
    (net (code "127") (name "unconnected-(IC7-SCK{slash}PB2-Pad7)") (class "Default")
      (node (ref "IC7") (pin "7") (pinfunction "SCK/PB2_7") (pintype "bidirectional"))
    )
    (net (code "128") (name "unconnected-(K5-Pad6)") (class "Default")
      (node (ref "K5") (pin "6") (pinfunction "6_6") (pintype "passive"))
    )
    (net (code "129") (name "unconnected-(U$1-VREF-Pad5)") (class "Default")
      (node (ref "U$1") (pin "5") (pinfunction "VREF_5") (pintype "output"))
    )
  )
)
